# Supply.net
KiCad netlist of a schematic drawn in Altium Designer
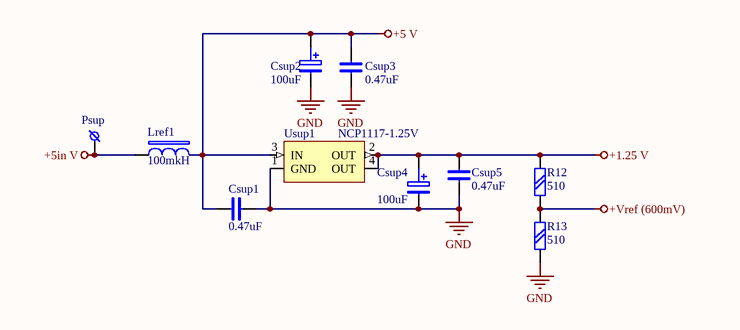
[diagram p0: Supply.SchDoc]

(export (version "E")
  (design (tool "Eeschema 10.0.6"))
  (components
    (comp (ref "Csup1") (value "0.47uF") (footprint "chip0805") (libsource (lib "*") (part "C")))
    (comp (ref "Csup2") (value "100uF") (footprint "CEL-SMD300") (libsource (lib "*") (part "C POL")))
    (comp (ref "Csup3") (value "0.47uF") (footprint "chip0805") (libsource (lib "*") (part "C")))
    (comp (ref "Csup4") (value "100uF") (footprint "CEL-SMD300") (libsource (lib "*") (part "C POL")))
    (comp (ref "Csup5") (value "0.47uF") (footprint "chip0805") (libsource (lib "*") (part "C")))
    (comp (ref "Lref1") (value "100mkH") (footprint "SDR0604") (libsource (lib "*") (part "DR")))
    (comp (ref "Psup") (value "KLEMME") (footprint "Pad12") (libsource (lib "vDevice") (part "KLEMME")))
    (comp (ref "R12") (value "510") (footprint "chip0805") (libsource (lib "vDevice") (part "R")))
    (comp (ref "R13") (value "510") (footprint "chip0805") (libsource (lib "vDevice") (part "R")))
    (comp (ref "Usup1")
      (value "NCP1117-1.25V")
      (footprint "TO-252")
      (libsource (lib "vAnalog") (part "NCP1117-3.3V"))
    )
  )
  (nets
    (net (code "1") (name "+1.25 V") (class "Default")
      (node (ref "Csup4") (pin "+") (pinfunction "+_+") (pintype "passive"))
      (node (ref "Csup5") (pin "1") (pinfunction "1_1") (pintype "passive"))
      (node (ref "R12") (pin "2") (pinfunction "2_2") (pintype "passive"))
      (node (ref "Usup1") (pin "2") (pinfunction "OUT_2") (pintype "output"))
      (node (ref "Usup1") (pin "4") (pinfunction "OUT_4") (pintype "passive"))
    )
    (net (code "2") (name "+5 V") (class "Default")
      (node (ref "Csup1") (pin "1") (pinfunction "1_1") (pintype "passive"))
      (node (ref "Csup2") (pin "+") (pinfunction "+_+") (pintype "passive"))
      (node (ref "Csup3") (pin "1") (pinfunction "1_1") (pintype "passive"))
      (node (ref "Lref1") (pin "2") (pinfunction "2_2") (pintype "passive"))
      (node (ref "Usup1") (pin "3") (pinfunction "IN_3") (pintype "input"))
    )
    (net (code "3") (name "+5in V") (class "Default")
      (node (ref "Lref1") (pin "1") (pinfunction "1_1") (pintype "passive"))
      (node (ref "Psup") (pin "PAD") (pinfunction "PAD_PAD") (pintype "passive"))
    )
    (net (code "4") (name "+Vref (600mV)") (class "Default")
      (node (ref "R12") (pin "1") (pinfunction "1_1") (pintype "passive"))
      (node (ref "R13") (pin "1") (pinfunction "1_1") (pintype "passive"))
    )
    (net (code "5") (name "GND") (class "Default")
      (node (ref "Csup1") (pin "2") (pinfunction "2_2") (pintype "passive"))
      (node (ref "Csup2") (pin "-") (pinfunction "-_-") (pintype "passive"))
      (node (ref "Csup3") (pin "2") (pinfunction "2_2") (pintype "passive"))
      (node (ref "Csup4") (pin "-") (pinfunction "-_-") (pintype "passive"))
      (node (ref "Csup5") (pin "2") (pinfunction "2_2") (pintype "passive"))
      (node (ref "R13") (pin "2") (pinfunction "2_2") (pintype "passive"))
      (node (ref "Usup1") (pin "1") (pinfunction "GND_1") (pintype "power_in"))
    )
  )
)
